# R201X.net
KiCad netlist of a schematic drawn in EAGLE
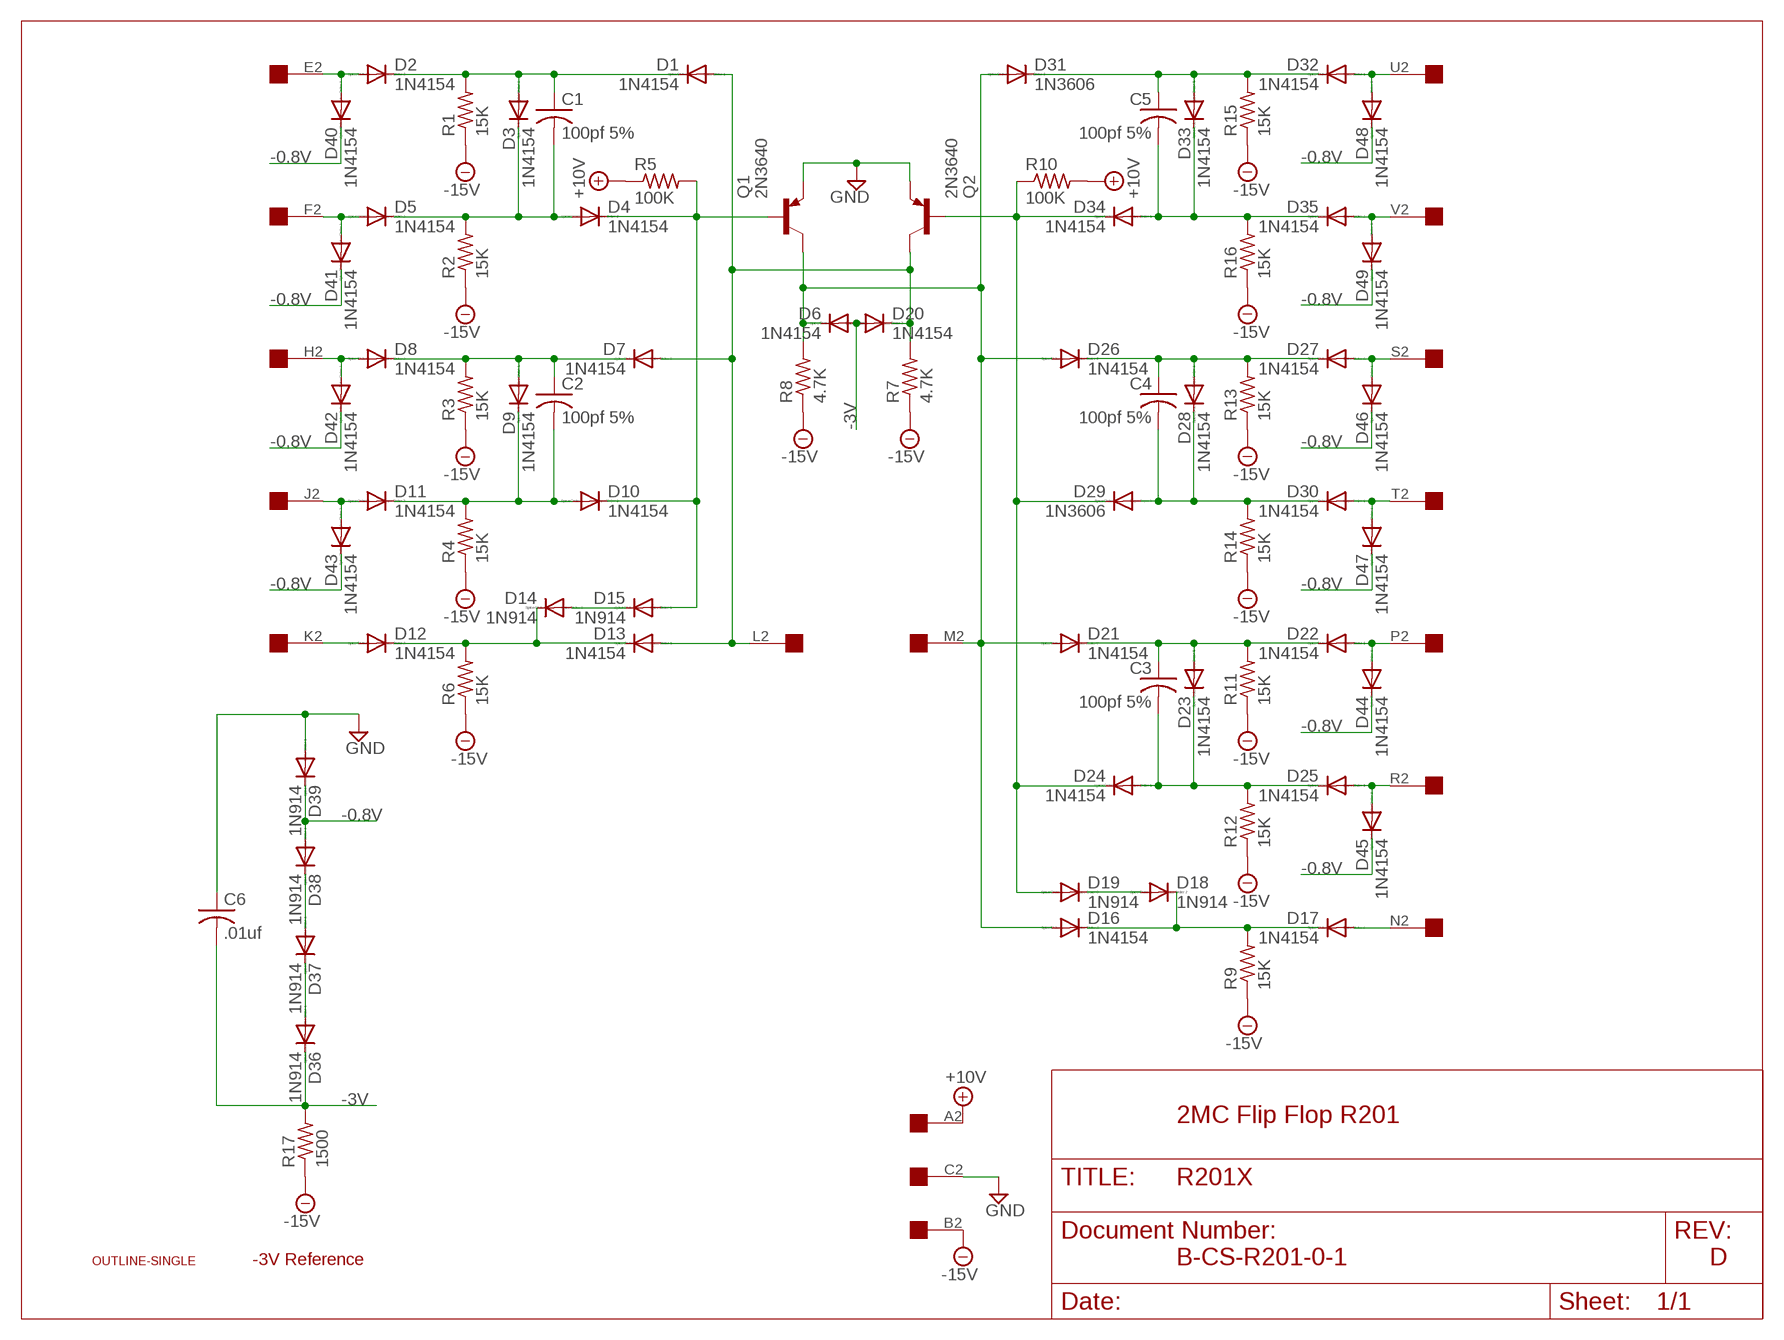
[diagram p0: schematic, sheet 1]

(export (version "E")
  (design (tool "Eeschema 10.0.6"))
  (components
    (comp (ref "C1")
      (value "100pf 5%")
      (footprint "eagle-import:C050-025X075")
      (libsource (lib "eagle-import") (part "C-US050-025X075"))
    )
    (comp (ref "C2")
      (value "100pf 5%")
      (footprint "eagle-import:C050-025X075")
      (libsource (lib "eagle-import") (part "C-US050-025X075"))
    )
    (comp (ref "C3")
      (value "100pf 5%")
      (footprint "eagle-import:C050-025X075")
      (libsource (lib "eagle-import") (part "C-US050-025X075"))
    )
    (comp (ref "C4")
      (value "100pf 5%")
      (footprint "eagle-import:C050-025X075")
      (libsource (lib "eagle-import") (part "C-US050-025X075"))
    )
    (comp (ref "C5")
      (value "100pf 5%")
      (footprint "eagle-import:C050-025X075")
      (libsource (lib "eagle-import") (part "C-US050-025X075"))
    )
    (comp (ref "C6")
      (value ".01uf")
      (footprint "eagle-import:C050-025X075")
      (libsource (lib "eagle-import") (part "C-US050-025X075"))
    )
    (comp (ref "D1")
      (value "1N4154")
      (footprint "eagle-import:DO35-10")
      (libsource (lib "eagle-import") (part "1N4148DO35-10"))
    )
    (comp (ref "D2")
      (value "1N4154")
      (footprint "eagle-import:DO35-10")
      (libsource (lib "eagle-import") (part "1N4148DO35-10"))
    )
    (comp (ref "D3")
      (value "1N4154")
      (footprint "eagle-import:DO35-10")
      (libsource (lib "eagle-import") (part "1N4148DO35-10"))
    )
    (comp (ref "D4")
      (value "1N4154")
      (footprint "eagle-import:DO35-10")
      (libsource (lib "eagle-import") (part "1N4148DO35-10"))
    )
    (comp (ref "D5")
      (value "1N4154")
      (footprint "eagle-import:DO35-10")
      (libsource (lib "eagle-import") (part "1N4148DO35-10"))
    )
    (comp (ref "D6")
      (value "1N4154")
      (footprint "eagle-import:DO35-10")
      (libsource (lib "eagle-import") (part "1N4148DO35-10"))
    )
    (comp (ref "D7")
      (value "1N4154")
      (footprint "eagle-import:DO35-10")
      (libsource (lib "eagle-import") (part "1N4148DO35-10"))
    )
    (comp (ref "D8")
      (value "1N4154")
      (footprint "eagle-import:DO35-10")
      (libsource (lib "eagle-import") (part "1N4148DO35-10"))
    )
    (comp (ref "D9")
      (value "1N4154")
      (footprint "eagle-import:DO35-10")
      (libsource (lib "eagle-import") (part "1N4148DO35-10"))
    )
    (comp (ref "D10")
      (value "1N4154")
      (footprint "eagle-import:DO35-10")
      (libsource (lib "eagle-import") (part "1N4148DO35-10"))
    )
    (comp (ref "D11")
      (value "1N4154")
      (footprint "eagle-import:DO35-10")
      (libsource (lib "eagle-import") (part "1N4148DO35-10"))
    )
    (comp (ref "D12")
      (value "1N4154")
      (footprint "eagle-import:DO35-10")
      (libsource (lib "eagle-import") (part "1N4148DO35-10"))
    )
    (comp (ref "D13")
      (value "1N4154")
      (footprint "eagle-import:DO35-10")
      (libsource (lib "eagle-import") (part "1N4148DO35-10"))
    )
    (comp (ref "D14")
      (value "1N914")
      (footprint "eagle-import:DO35-10")
      (libsource (lib "eagle-import") (part "1N4148DO35-10"))
    )
    (comp (ref "D15")
      (value "1N914")
      (footprint "eagle-import:DO35-10")
      (libsource (lib "eagle-import") (part "1N4148DO35-10"))
    )
    (comp (ref "D16")
      (value "1N4154")
      (footprint "eagle-import:DO35-10")
      (libsource (lib "eagle-import") (part "1N4148DO35-10"))
    )
    (comp (ref "D17")
      (value "1N4154")
      (footprint "eagle-import:DO35-10")
      (libsource (lib "eagle-import") (part "1N4148DO35-10"))
    )
    (comp (ref "D18")
      (value "1N914")
      (footprint "eagle-import:DO35-10")
      (libsource (lib "eagle-import") (part "1N4148DO35-10"))
    )
    (comp (ref "D19")
      (value "1N914")
      (footprint "eagle-import:DO35-10")
      (libsource (lib "eagle-import") (part "1N4148DO35-10"))
    )
    (comp (ref "D20")
      (value "1N4154")
      (footprint "eagle-import:DO35-10")
      (libsource (lib "eagle-import") (part "1N4148DO35-10"))
    )
    (comp (ref "D21")
      (value "1N4154")
      (footprint "eagle-import:DO35-10")
      (libsource (lib "eagle-import") (part "1N4148DO35-10"))
    )
    (comp (ref "D22")
      (value "1N4154")
      (footprint "eagle-import:DO35-10")
      (libsource (lib "eagle-import") (part "1N4148DO35-10"))
    )
    (comp (ref "D23")
      (value "1N4154")
      (footprint "eagle-import:DO35-10")
      (libsource (lib "eagle-import") (part "1N4148DO35-10"))
    )
    (comp (ref "D24")
      (value "1N4154")
      (footprint "eagle-import:DO35-10")
      (libsource (lib "eagle-import") (part "1N4148DO35-10"))
    )
    (comp (ref "D25")
      (value "1N4154")
      (footprint "eagle-import:DO35-10")
      (libsource (lib "eagle-import") (part "1N4148DO35-10"))
    )
    (comp (ref "D26")
      (value "1N4154")
      (footprint "eagle-import:DO35-10")
      (libsource (lib "eagle-import") (part "1N4148DO35-10"))
    )
    (comp (ref "D27")
      (value "1N4154")
      (footprint "eagle-import:DO35-10")
      (libsource (lib "eagle-import") (part "1N4148DO35-10"))
    )
    (comp (ref "D28")
      (value "1N4154")
      (footprint "eagle-import:DO35-10")
      (libsource (lib "eagle-import") (part "1N4148DO35-10"))
    )
    (comp (ref "D29")
      (value "1N3606")
      (footprint "eagle-import:DO35-10")
      (libsource (lib "eagle-import") (part "1N4148DO35-10"))
    )
    (comp (ref "D30")
      (value "1N4154")
      (footprint "eagle-import:DO35-10")
      (libsource (lib "eagle-import") (part "1N4148DO35-10"))
    )
    (comp (ref "D31")
      (value "1N3606")
      (footprint "eagle-import:DO35-10")
      (libsource (lib "eagle-import") (part "1N4148DO35-10"))
    )
    (comp (ref "D32")
      (value "1N4154")
      (footprint "eagle-import:DO35-10")
      (libsource (lib "eagle-import") (part "1N4148DO35-10"))
    )
    (comp (ref "D33")
      (value "1N4154")
      (footprint "eagle-import:DO35-10")
      (libsource (lib "eagle-import") (part "1N4148DO35-10"))
    )
    (comp (ref "D34")
      (value "1N4154")
      (footprint "eagle-import:DO35-10")
      (libsource (lib "eagle-import") (part "1N4148DO35-10"))
    )
    (comp (ref "D35")
      (value "1N4154")
      (footprint "eagle-import:DO35-10")
      (libsource (lib "eagle-import") (part "1N4148DO35-10"))
    )
    (comp (ref "D36")
      (value "1N914")
      (footprint "eagle-import:DO35-10")
      (libsource (lib "eagle-import") (part "1N4148DO35-10"))
    )
    (comp (ref "D37")
      (value "1N914")
      (footprint "eagle-import:DO35-10")
      (libsource (lib "eagle-import") (part "1N4148DO35-10"))
    )
    (comp (ref "D38")
      (value "1N914")
      (footprint "eagle-import:DO35-10")
      (libsource (lib "eagle-import") (part "1N4148DO35-10"))
    )
    (comp (ref "D39")
      (value "1N914")
      (footprint "eagle-import:DO35-10")
      (libsource (lib "eagle-import") (part "1N4148DO35-10"))
    )
    (comp (ref "D40")
      (value "1N4154")
      (footprint "eagle-import:DO35-10")
      (libsource (lib "eagle-import") (part "1N4148DO35-10"))
    )
    (comp (ref "D41")
      (value "1N4154")
      (footprint "eagle-import:DO35-10")
      (libsource (lib "eagle-import") (part "1N4148DO35-10"))
    )
    (comp (ref "D42")
      (value "1N4154")
      (footprint "eagle-import:DO35-10")
      (libsource (lib "eagle-import") (part "1N4148DO35-10"))
    )
    (comp (ref "D43")
      (value "1N4154")
      (footprint "eagle-import:DO35-10")
      (libsource (lib "eagle-import") (part "1N4148DO35-10"))
    )
    (comp (ref "D44")
      (value "1N4154")
      (footprint "eagle-import:DO35-10")
      (libsource (lib "eagle-import") (part "1N4148DO35-10"))
    )
    (comp (ref "D45")
      (value "1N4154")
      (footprint "eagle-import:DO35-10")
      (libsource (lib "eagle-import") (part "1N4148DO35-10"))
    )
    (comp (ref "D46")
      (value "1N4154")
      (footprint "eagle-import:DO35-10")
      (libsource (lib "eagle-import") (part "1N4148DO35-10"))
    )
    (comp (ref "D47")
      (value "1N4154")
      (footprint "eagle-import:DO35-10")
      (libsource (lib "eagle-import") (part "1N4148DO35-10"))
    )
    (comp (ref "D48")
      (value "1N4154")
      (footprint "eagle-import:DO35-10")
      (libsource (lib "eagle-import") (part "1N4148DO35-10"))
    )
    (comp (ref "D49")
      (value "1N4154")
      (footprint "eagle-import:DO35-10")
      (libsource (lib "eagle-import") (part "1N4148DO35-10"))
    )
    (comp (ref "Q1")
      (value "2N3640")
      (footprint "eagle-import:TO39")
      (libsource (lib "eagle-import") (part "2N3637"))
    )
    (comp (ref "Q2")
      (value "2N3640")
      (footprint "eagle-import:TO39")
      (libsource (lib "eagle-import") (part "2N3637"))
    )
    (comp (ref "R1")
      (value "15K")
      (footprint "eagle-import:0207_10")
      (libsource (lib "eagle-import") (part "R-US_0207/10"))
    )
    (comp (ref "R2")
      (value "15K")
      (footprint "eagle-import:0207_10")
      (libsource (lib "eagle-import") (part "R-US_0207/10"))
    )
    (comp (ref "R3")
      (value "15K")
      (footprint "eagle-import:0207_10")
      (libsource (lib "eagle-import") (part "R-US_0207/10"))
    )
    (comp (ref "R4")
      (value "15K")
      (footprint "eagle-import:0207_10")
      (libsource (lib "eagle-import") (part "R-US_0207/10"))
    )
    (comp (ref "R5")
      (value "100K")
      (footprint "eagle-import:0207_10")
      (libsource (lib "eagle-import") (part "R-US_0207/10"))
    )
    (comp (ref "R6")
      (value "15K")
      (footprint "eagle-import:0207_10")
      (libsource (lib "eagle-import") (part "R-US_0207/10"))
    )
    (comp (ref "R7")
      (value "4.7K")
      (footprint "eagle-import:0207_10")
      (libsource (lib "eagle-import") (part "R-US_0207/10"))
    )
    (comp (ref "R8")
      (value "4.7K")
      (footprint "eagle-import:0207_10")
      (libsource (lib "eagle-import") (part "R-US_0207/10"))
    )
    (comp (ref "R9")
      (value "15K")
      (footprint "eagle-import:0207_10")
      (libsource (lib "eagle-import") (part "R-US_0207/10"))
    )
    (comp (ref "R10")
      (value "100K")
      (footprint "eagle-import:0207_10")
      (libsource (lib "eagle-import") (part "R-US_0207/10"))
    )
    (comp (ref "R11")
      (value "15K")
      (footprint "eagle-import:0207_10")
      (libsource (lib "eagle-import") (part "R-US_0207/10"))
    )
    (comp (ref "R12")
      (value "15K")
      (footprint "eagle-import:0207_10")
      (libsource (lib "eagle-import") (part "R-US_0207/10"))
    )
    (comp (ref "R13")
      (value "15K")
      (footprint "eagle-import:0207_10")
      (libsource (lib "eagle-import") (part "R-US_0207/10"))
    )
    (comp (ref "R14")
      (value "15K")
      (footprint "eagle-import:0207_10")
      (libsource (lib "eagle-import") (part "R-US_0207/10"))
    )
    (comp (ref "R15")
      (value "15K")
      (footprint "eagle-import:0207_10")
      (libsource (lib "eagle-import") (part "R-US_0207/10"))
    )
    (comp (ref "R16")
      (value "15K")
      (footprint "eagle-import:0207_10")
      (libsource (lib "eagle-import") (part "R-US_0207/10"))
    )
    (comp (ref "R17")
      (value "1500")
      (footprint "eagle-import:0207_10")
      (libsource (lib "eagle-import") (part "R-US_0207/10"))
    )
    (comp (ref "U$1")
      (value "OUTLINE-SINGLE")
      (footprint "eagle-import:SINGLE")
      (libsource (lib "eagle-import") (part "OUTLINE-SINGLE"))
    )
    (comp (ref "U$2")
      (value "EDGE-1")
      (footprint "eagle-import:EDGE-CON1")
      (libsource (lib "eagle-import") (part "EDGE-1"))
    )
  )
  (nets
    (net (code "1") (name "+10V") (class "Default")
      (node (ref "R10") (pin "2") (pinfunction "2_2") (pintype "passive"))
      (node (ref "R5") (pin "1") (pinfunction "1_1") (pintype "passive"))
      (node (ref "U$2") (pin "A2") (pinfunction "1_A2") (pintype "bidirectional"))
    )
    (net (code "2") (name "-15V") (class "Default")
      (node (ref "R1") (pin "1") (pinfunction "1_1") (pintype "passive"))
      (node (ref "R11") (pin "1") (pinfunction "1_1") (pintype "passive"))
      (node (ref "R12") (pin "1") (pinfunction "1_1") (pintype "passive"))
      (node (ref "R13") (pin "1") (pinfunction "1_1") (pintype "passive"))
      (node (ref "R14") (pin "1") (pinfunction "1_1") (pintype "passive"))
      (node (ref "R15") (pin "1") (pinfunction "1_1") (pintype "passive"))
      (node (ref "R16") (pin "1") (pinfunction "1_1") (pintype "passive"))
      (node (ref "R17") (pin "1") (pinfunction "1_1") (pintype "passive"))
      (node (ref "R2") (pin "1") (pinfunction "1_1") (pintype "passive"))
      (node (ref "R3") (pin "1") (pinfunction "1_1") (pintype "passive"))
      (node (ref "R4") (pin "1") (pinfunction "1_1") (pintype "passive"))
      (node (ref "R6") (pin "1") (pinfunction "1_1") (pintype "passive"))
      (node (ref "R7") (pin "1") (pinfunction "1_1") (pintype "passive"))
      (node (ref "R8") (pin "1") (pinfunction "1_1") (pintype "passive"))
      (node (ref "R9") (pin "1") (pinfunction "1_1") (pintype "passive"))
      (node (ref "U$2") (pin "B2") (pinfunction "1_B2") (pintype "bidirectional"))
    )
    (net (code "3") (name "/-0.8V") (class "Default")
      (node (ref "D38") (pin "A") (pinfunction "A_A") (pintype "passive"))
      (node (ref "D39") (pin "C") (pinfunction "C_C") (pintype "passive"))
      (node (ref "D40") (pin "C") (pinfunction "C_C") (pintype "passive"))
      (node (ref "D41") (pin "C") (pinfunction "C_C") (pintype "passive"))
      (node (ref "D42") (pin "C") (pinfunction "C_C") (pintype "passive"))
      (node (ref "D43") (pin "C") (pinfunction "C_C") (pintype "passive"))
      (node (ref "D44") (pin "C") (pinfunction "C_C") (pintype "passive"))
      (node (ref "D45") (pin "C") (pinfunction "C_C") (pintype "passive"))
      (node (ref "D46") (pin "C") (pinfunction "C_C") (pintype "passive"))
      (node (ref "D47") (pin "C") (pinfunction "C_C") (pintype "passive"))
      (node (ref "D48") (pin "C") (pinfunction "C_C") (pintype "passive"))
      (node (ref "D49") (pin "C") (pinfunction "C_C") (pintype "passive"))
    )
    (net (code "4") (name "/-3V") (class "Default")
      (node (ref "C6") (pin "2") (pinfunction "2_2") (pintype "passive"))
      (node (ref "D20") (pin "A") (pinfunction "A_A") (pintype "passive"))
      (node (ref "D36") (pin "C") (pinfunction "C_C") (pintype "passive"))
      (node (ref "D6") (pin "A") (pinfunction "A_A") (pintype "passive"))
      (node (ref "R17") (pin "2") (pinfunction "2_2") (pintype "passive"))
    )
    (net (code "5") (name "GND") (class "Default")
      (node (ref "C6") (pin "1") (pinfunction "1_1") (pintype "passive"))
      (node (ref "D39") (pin "A") (pinfunction "A_A") (pintype "passive"))
      (node (ref "Q1") (pin "1") (pinfunction "E_1") (pintype "passive"))
      (node (ref "Q2") (pin "1") (pinfunction "E_1") (pintype "passive"))
      (node (ref "U$2") (pin "C2") (pinfunction "1_C2") (pintype "bidirectional"))
    )
    (net (code "6") (name "Net-(C1-Pad1)") (class "Default")
      (node (ref "C1") (pin "1") (pinfunction "1_1") (pintype "passive"))
      (node (ref "D1") (pin "C") (pinfunction "C_C") (pintype "passive"))
      (node (ref "D2") (pin "C") (pinfunction "C_C") (pintype "passive"))
      (node (ref "D3") (pin "A") (pinfunction "A_A") (pintype "passive"))
      (node (ref "R1") (pin "2") (pinfunction "2_2") (pintype "passive"))
    )
    (net (code "7") (name "Net-(C1-Pad2)") (class "Default")
      (node (ref "C1") (pin "2") (pinfunction "2_2") (pintype "passive"))
      (node (ref "D3") (pin "C") (pinfunction "C_C") (pintype "passive"))
      (node (ref "D4") (pin "A") (pinfunction "A_A") (pintype "passive"))
      (node (ref "D5") (pin "C") (pinfunction "C_C") (pintype "passive"))
      (node (ref "R2") (pin "2") (pinfunction "2_2") (pintype "passive"))
    )
    (net (code "8") (name "Net-(C2-Pad1)") (class "Default")
      (node (ref "C2") (pin "1") (pinfunction "1_1") (pintype "passive"))
      (node (ref "D7") (pin "C") (pinfunction "C_C") (pintype "passive"))
      (node (ref "D8") (pin "C") (pinfunction "C_C") (pintype "passive"))
      (node (ref "D9") (pin "A") (pinfunction "A_A") (pintype "passive"))
      (node (ref "R3") (pin "2") (pinfunction "2_2") (pintype "passive"))
    )
    (net (code "9") (name "Net-(C2-Pad2)") (class "Default")
      (node (ref "C2") (pin "2") (pinfunction "2_2") (pintype "passive"))
      (node (ref "D10") (pin "A") (pinfunction "A_A") (pintype "passive"))
      (node (ref "D11") (pin "C") (pinfunction "C_C") (pintype "passive"))
      (node (ref "D9") (pin "C") (pinfunction "C_C") (pintype "passive"))
      (node (ref "R4") (pin "2") (pinfunction "2_2") (pintype "passive"))
    )
    (net (code "10") (name "Net-(C3-Pad1)") (class "Default")
      (node (ref "C3") (pin "1") (pinfunction "1_1") (pintype "passive"))
      (node (ref "D21") (pin "C") (pinfunction "C_C") (pintype "passive"))
      (node (ref "D22") (pin "C") (pinfunction "C_C") (pintype "passive"))
      (node (ref "D23") (pin "A") (pinfunction "A_A") (pintype "passive"))
      (node (ref "R11") (pin "2") (pinfunction "2_2") (pintype "passive"))
    )
    (net (code "11") (name "Net-(C3-Pad2)") (class "Default")
      (node (ref "C3") (pin "2") (pinfunction "2_2") (pintype "passive"))
      (node (ref "D23") (pin "C") (pinfunction "C_C") (pintype "passive"))
      (node (ref "D24") (pin "A") (pinfunction "A_A") (pintype "passive"))
      (node (ref "D25") (pin "C") (pinfunction "C_C") (pintype "passive"))
      (node (ref "R12") (pin "2") (pinfunction "2_2") (pintype "passive"))
    )
    (net (code "12") (name "Net-(C4-Pad1)") (class "Default")
      (node (ref "C4") (pin "1") (pinfunction "1_1") (pintype "passive"))
      (node (ref "D26") (pin "C") (pinfunction "C_C") (pintype "passive"))
      (node (ref "D27") (pin "C") (pinfunction "C_C") (pintype "passive"))
      (node (ref "D28") (pin "A") (pinfunction "A_A") (pintype "passive"))
      (node (ref "R13") (pin "2") (pinfunction "2_2") (pintype "passive"))
    )
    (net (code "13") (name "Net-(C4-Pad2)") (class "Default")
      (node (ref "C4") (pin "2") (pinfunction "2_2") (pintype "passive"))
      (node (ref "D28") (pin "C") (pinfunction "C_C") (pintype "passive"))
      (node (ref "D29") (pin "A") (pinfunction "A_A") (pintype "passive"))
      (node (ref "D30") (pin "C") (pinfunction "C_C") (pintype "passive"))
      (node (ref "R14") (pin "2") (pinfunction "2_2") (pintype "passive"))
    )
    (net (code "14") (name "Net-(C5-Pad1)") (class "Default")
      (node (ref "C5") (pin "1") (pinfunction "1_1") (pintype "passive"))
      (node (ref "D31") (pin "C") (pinfunction "C_C") (pintype "passive"))
      (node (ref "D32") (pin "C") (pinfunction "C_C") (pintype "passive"))
      (node (ref "D33") (pin "A") (pinfunction "A_A") (pintype "passive"))
      (node (ref "R15") (pin "2") (pinfunction "2_2") (pintype "passive"))
    )
    (net (code "15") (name "Net-(C5-Pad2)") (class "Default")
      (node (ref "C5") (pin "2") (pinfunction "2_2") (pintype "passive"))
      (node (ref "D33") (pin "C") (pinfunction "C_C") (pintype "passive"))
      (node (ref "D34") (pin "A") (pinfunction "A_A") (pintype "passive"))
      (node (ref "D35") (pin "C") (pinfunction "C_C") (pintype "passive"))
      (node (ref "R16") (pin "2") (pinfunction "2_2") (pintype "passive"))
    )
    (net (code "16") (name "Net-(D12-PadC)") (class "Default")
      (node (ref "D12") (pin "C") (pinfunction "C_C") (pintype "passive"))
      (node (ref "D13") (pin "C") (pinfunction "C_C") (pintype "passive"))
      (node (ref "D14") (pin "C") (pinfunction "C_C") (pintype "passive"))
      (node (ref "R6") (pin "2") (pinfunction "2_2") (pintype "passive"))
    )
    (net (code "17") (name "Net-(D14-PadA)") (class "Default")
      (node (ref "D14") (pin "A") (pinfunction "A_A") (pintype "passive"))
      (node (ref "D15") (pin "C") (pinfunction "C_C") (pintype "passive"))
    )
    (net (code "18") (name "Net-(D16-PadC)") (class "Default")
      (node (ref "D16") (pin "C") (pinfunction "C_C") (pintype "passive"))
      (node (ref "D17") (pin "C") (pinfunction "C_C") (pintype "passive"))
      (node (ref "D18") (pin "C") (pinfunction "C_C") (pintype "passive"))
      (node (ref "R9") (pin "2") (pinfunction "2_2") (pintype "passive"))
    )
    (net (code "19") (name "Net-(D18-PadA)") (class "Default")
      (node (ref "D18") (pin "A") (pinfunction "A_A") (pintype "passive"))
      (node (ref "D19") (pin "C") (pinfunction "C_C") (pintype "passive"))
    )
    (net (code "20") (name "Net-(D36-PadA)") (class "Default")
      (node (ref "D36") (pin "A") (pinfunction "A_A") (pintype "passive"))
      (node (ref "D37") (pin "C") (pinfunction "C_C") (pintype "passive"))
    )
    (net (code "21") (name "Net-(D37-PadA)") (class "Default")
      (node (ref "D37") (pin "A") (pinfunction "A_A") (pintype "passive"))
      (node (ref "D38") (pin "C") (pinfunction "C_C") (pintype "passive"))
    )
    (net (code "22") (name "Net-(Q1-B)") (class "Default")
      (node (ref "D10") (pin "C") (pinfunction "C_C") (pintype "passive"))
      (node (ref "D15") (pin "A") (pinfunction "A_A") (pintype "passive"))
      (node (ref "D4") (pin "C") (pinfunction "C_C") (pintype "passive"))
      (node (ref "Q1") (pin "2") (pinfunction "B_2") (pintype "passive"))
      (node (ref "R5") (pin "2") (pinfunction "2_2") (pintype "passive"))
    )
    (net (code "23") (name "Net-(Q1-C)") (class "Default")
      (node (ref "D16") (pin "A") (pinfunction "A_A") (pintype "passive"))
      (node (ref "D21") (pin "A") (pinfunction "A_A") (pintype "passive"))
      (node (ref "D26") (pin "A") (pinfunction "A_A") (pintype "passive"))
      (node (ref "D31") (pin "A") (pinfunction "A_A") (pintype "passive"))
      (node (ref "D6") (pin "C") (pinfunction "C_C") (pintype "passive"))
      (node (ref "Q1") (pin "3") (pinfunction "C_3") (pintype "passive"))
      (node (ref "R8") (pin "2") (pinfunction "2_2") (pintype "passive"))
      (node (ref "U$2") (pin "M2") (pinfunction "1_M2") (pintype "bidirectional"))
    )
    (net (code "24") (name "Net-(Q2-B)") (class "Default")
      (node (ref "D19") (pin "A") (pinfunction "A_A") (pintype "passive"))
      (node (ref "D24") (pin "C") (pinfunction "C_C") (pintype "passive"))
      (node (ref "D29") (pin "C") (pinfunction "C_C") (pintype "passive"))
      (node (ref "D34") (pin "C") (pinfunction "C_C") (pintype "passive"))
      (node (ref "Q2") (pin "2") (pinfunction "B_2") (pintype "passive"))
      (node (ref "R10") (pin "1") (pinfunction "1_1") (pintype "passive"))
    )
    (net (code "25") (name "Net-(Q2-C)") (class "Default")
      (node (ref "D1") (pin "A") (pinfunction "A_A") (pintype "passive"))
      (node (ref "D13") (pin "A") (pinfunction "A_A") (pintype "passive"))
      (node (ref "D20") (pin "C") (pinfunction "C_C") (pintype "passive"))
      (node (ref "D7") (pin "A") (pinfunction "A_A") (pintype "passive"))
      (node (ref "Q2") (pin "3") (pinfunction "C_3") (pintype "passive"))
      (node (ref "R7") (pin "2") (pinfunction "2_2") (pintype "passive"))
      (node (ref "U$2") (pin "L2") (pinfunction "1_L2") (pintype "bidirectional"))
    )
    (net (code "26") (name "Net-(U$2E-1)") (class "Default")
      (node (ref "D2") (pin "A") (pinfunction "A_A") (pintype "passive"))
      (node (ref "D40") (pin "A") (pinfunction "A_A") (pintype "passive"))
      (node (ref "U$2") (pin "E2") (pinfunction "1_E2") (pintype "bidirectional"))
    )
    (net (code "27") (name "Net-(U$2F-1)") (class "Default")
      (node (ref "D41") (pin "A") (pinfunction "A_A") (pintype "passive"))
      (node (ref "D5") (pin "A") (pinfunction "A_A") (pintype "passive"))
      (node (ref "U$2") (pin "F2") (pinfunction "1_F2") (pintype "bidirectional"))
    )
    (net (code "28") (name "Net-(U$2G-1)") (class "Default")
      (node (ref "D42") (pin "A") (pinfunction "A_A") (pintype "passive"))
      (node (ref "D8") (pin "A") (pinfunction "A_A") (pintype "passive"))
      (node (ref "U$2") (pin "H2") (pinfunction "1_H2") (pintype "bidirectional"))
    )
    (net (code "29") (name "Net-(U$2H-1)") (class "Default")
      (node (ref "D11") (pin "A") (pinfunction "A_A") (pintype "passive"))
      (node (ref "D43") (pin "A") (pinfunction "A_A") (pintype "passive"))
      (node (ref "U$2") (pin "J2") (pinfunction "1_J2") (pintype "bidirectional"))
    )
    (net (code "30") (name "Net-(U$2I-1)") (class "Default")
      (node (ref "D12") (pin "A") (pinfunction "A_A") (pintype "passive"))
      (node (ref "U$2") (pin "K2") (pinfunction "1_K2") (pintype "bidirectional"))
    )
    (net (code "31") (name "Net-(U$2L-1)") (class "Default")
      (node (ref "D17") (pin "A") (pinfunction "A_A") (pintype "passive"))
      (node (ref "U$2") (pin "N2") (pinfunction "1_N2") (pintype "bidirectional"))
    )
    (net (code "32") (name "Net-(U$2M-1)") (class "Default")
      (node (ref "D22") (pin "A") (pinfunction "A_A") (pintype "passive"))
      (node (ref "D44") (pin "A") (pinfunction "A_A") (pintype "passive"))
      (node (ref "U$2") (pin "P2") (pinfunction "1_P2") (pintype "bidirectional"))
    )
    (net (code "33") (name "Net-(U$2N-1)") (class "Default")
      (node (ref "D25") (pin "A") (pinfunction "A_A") (pintype "passive"))
      (node (ref "D45") (pin "A") (pinfunction "A_A") (pintype "passive"))
      (node (ref "U$2") (pin "R2") (pinfunction "1_R2") (pintype "bidirectional"))
    )
    (net (code "34") (name "Net-(U$2O-1)") (class "Default")
      (node (ref "D27") (pin "A") (pinfunction "A_A") (pintype "passive"))
      (node (ref "D46") (pin "A") (pinfunction "A_A") (pintype "passive"))
      (node (ref "U$2") (pin "S2") (pinfunction "1_S2") (pintype "bidirectional"))
    )
    (net (code "35") (name "Net-(U$2P-1)") (class "Default")
      (node (ref "D30") (pin "A") (pinfunction "A_A") (pintype "passive"))
      (node (ref "D47") (pin "A") (pinfunction "A_A") (pintype "passive"))
      (node (ref "U$2") (pin "T2") (pinfunction "1_T2") (pintype "bidirectional"))
    )
    (net (code "36") (name "Net-(U$2Q-1)") (class "Default")
      (node (ref "D32") (pin "A") (pinfunction "A_A") (pintype "passive"))
      (node (ref "D48") (pin "A") (pinfunction "A_A") (pintype "passive"))
      (node (ref "U$2") (pin "U2") (pinfunction "1_U2") (pintype "bidirectional"))
    )
    (net (code "37") (name "Net-(U$2R-1)") (class "Default")
      (node (ref "D35") (pin "A") (pinfunction "A_A") (pintype "passive"))
      (node (ref "D49") (pin "A") (pinfunction "A_A") (pintype "passive"))
      (node (ref "U$2") (pin "V2") (pinfunction "1_V2") (pintype "bidirectional"))
    )
  )
)
